# Ultrasonic_Localisation.net
KiCad netlist of a schematic drawn in Altium Designer
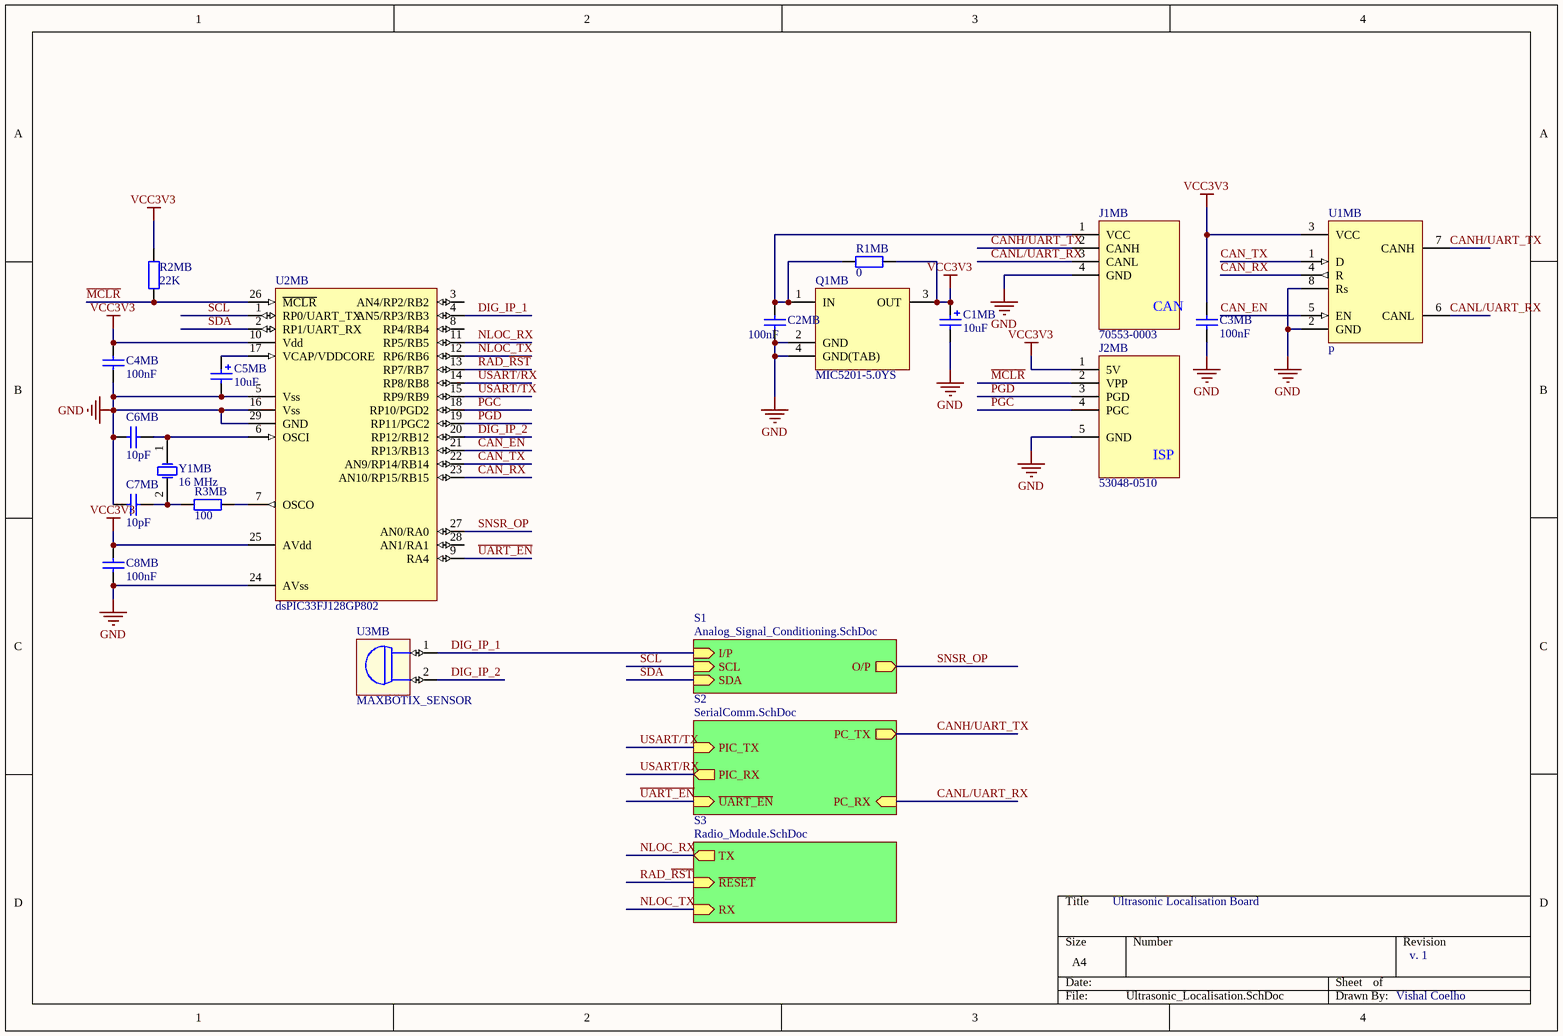
[diagram p0: Ultrasonic_Localisation.SchDoc]

(export (version "E")
  (design (tool "Eeschema 10.0.6"))
  (components
    (comp (ref "C1MB")
      (value "10uF")
      (footprint "TC3528-1411")
      (description "Polarized Capacitor (Surface Mount)")
      (fields (field (name "MANUFACTURER") "AVX") (field (name "Comment") "TPSB106K016R0800"))
      (libsource (lib "Comp") (part "Cap Pol"))
    )
    (comp (ref "C2MB")
      (value "100nF")
      (footprint "CC1608-0603")
      (description "Capacitor")
      (fields (field (name "MANUFACTURER") "Taiyo Yuden") (field (name "Comment") "UMK107BJ104KA-T"))
      (libsource (lib "Comp") (part "Cap"))
    )
    (comp (ref "C3MB")
      (value "100nF")
      (footprint "CC1608-0603")
      (description "Capacitor")
      (fields (field (name "MANUFACTURER") "Taiyo Yuden") (field (name "Comment") "UMK107BJ104KA-T"))
      (libsource (lib "Comp") (part "Cap"))
    )
    (comp (ref "C4MB")
      (value "100nF")
      (footprint "CC1608-0603")
      (description "Capacitor")
      (fields (field (name "MANUFACTURER") "Taiyo Yuden") (field (name "Comment") "UMK107BJ104KA-T"))
      (libsource (lib "Comp") (part "Cap"))
    )
    (comp (ref "C5MB")
      (value "10uF")
      (footprint "TC3528-1411")
      (description "Polarized Capacitor (Surface Mount)")
      (fields (field (name "MANUFACTURER") "AVX") (field (name "Comment") "TPSB106K016R0800"))
      (libsource (lib "Comp") (part "Cap Pol"))
    )
    (comp (ref "C6MB")
      (value "10pF")
      (footprint "CC1608-0603")
      (description "Capacitor")
      (fields (field (name "MANUFACTURER") "Panasonic") (field (name "Comment") "Cap"))
      (libsource (lib "Comp") (part "Cap"))
    )
    (comp (ref "C7MB")
      (value "10pF")
      (footprint "CC1608-0603")
      (description "Capacitor")
      (fields (field (name "MANUFACTURER") "Panasonic") (field (name "Comment") "Cap"))
      (libsource (lib "Comp") (part "Cap"))
    )
    (comp (ref "C8MB")
      (value "100nF")
      (footprint "CC1608-0603")
      (description "Capacitor")
      (fields (field (name "MANUFACTURER") "Taiyo Yuden") (field (name "Comment") "UMK107BJ104KA-T"))
      (libsource (lib "Comp") (part "Cap"))
    )
    (comp (ref "J1MB")
      (value "70553-0003")
      (footprint "CON_CAN_Device-4")
      (description "4 pin CAN Connector 2.54mm pitch")
      (fields (field (name "MANUFACTURER") "Molex"))
      (libsource (lib "Comp") (part "CON_CAN_DEVICE"))
    )
    (comp (ref "J2MB")
      (value "53048-0510")
      (footprint "CON_ISP")
      (description "6 pin header - 1.25mm pitch horizontal")
      (fields (field (name "MANUFACTURER") "Molex"))
      (libsource (lib "Comp") (part "CON_ISP_Header_5p_1.25mm_horizontal"))
    )
    (comp (ref "Q1MB")
      (value "MIC5201-5.0YS")
      (footprint "DSO-G3")
      (description "5V LDO 200mA")
      (fields (field (name "MANUFACTURER") "Micrel"))
      (libsource (lib "Comp") (part "MIC5201-5.0YS"))
    )
    (comp (ref "R1MB")
      (value "0")
      (footprint "CR1608-0603")
      (description "Resistor")
      (fields (field (name "Comment") "Res"))
      (libsource (lib "Comp") (part "Res"))
    )
    (comp (ref "R2MB")
      (value "22K")
      (footprint "CR1608-0603")
      (description "Resistor")
      (fields (field (name "Comment") "Res"))
      (libsource (lib "") (part "Res_1"))
    )
    (comp (ref "R3MB")
      (value "100")
      (footprint "CR1608-0603")
      (description "Resistor")
      (fields (field (name "Comment") "Res"))
      (libsource (lib "Comp") (part "Res"))
    )
    (comp (ref "U1MB")
      (value "p")
      (footprint "SO-G8/E2.9")
      (description "3.3V CAN Transceiver")
      (fields (field (name "MANUFACTURER") "Texas Instruments"))
      (libsource (lib "*") (part "SN65HVD234D"))
    )
    (comp (ref "U2MB")
      (value "dsPIC33FJ128GP802")
      (footprint "QFN6X6-28")
      (description "dsPIC33FJ128GP802 with 2 UART's")
      (fields (field (name "MANUFACTURER") "MicroChip"))
      (libsource (lib "Comp") (part "dsPIC33FJ128GP802"))
    )
    (comp (ref "U3MB")
      (value "MAXBOTIX_SENSOR")
      (footprint "Maxbotix Sensor")
      (description "Maxbotix Ultrasonic Sensor")
      (fields (field (name "MANUFACTURER") "Maxbotix"))
      (libsource (lib "*") (part "MAXBOTIX_SENSOR"))
    )
    (comp (ref "Y1MB")
      (value "16 MHz")
      (footprint "Footprints:CS10")
      (description "Crystal Oscillator")
      (fields (field (name "MANUFACTURER") "Citizen") (field (name "Comment") "CS10-16.000MABJ-UT"))
      (libsource (lib "Comp") (part "CS10"))
    )
  )
  (nets
    (net (code "1") (name "/CANH{slash}UART_TX") (class "Default")
      (node (ref "J1MB") (pin "2") (pinfunction "CANH_2") (pintype "passive"))
      (node (ref "U1MB") (pin "7") (pinfunction "CANH_7") (pintype "passive"))
    )
    (net (code "2") (name "/CANL{slash}UART_RX") (class "Default")
      (node (ref "J1MB") (pin "3") (pinfunction "CANL_3") (pintype "passive"))
      (node (ref "U1MB") (pin "6") (pinfunction "CANL_6") (pintype "passive"))
    )
    (net (code "3") (name "/CAN_EN") (class "Default")
      (node (ref "U1MB") (pin "5") (pinfunction "EN_5") (pintype "input"))
      (node (ref "U2MB") (pin "21") (pinfunction "RP13/RB13_21") (pintype "bidirectional"))
    )
    (net (code "4") (name "/CAN_RX") (class "Default")
      (node (ref "U1MB") (pin "4") (pinfunction "R_4") (pintype "output"))
      (node (ref "U2MB") (pin "23") (pinfunction "AN10/RP15/RB15_23") (pintype "bidirectional"))
    )
    (net (code "5") (name "/CAN_TX") (class "Default")
      (node (ref "U1MB") (pin "1") (pinfunction "D_1") (pintype "input"))
      (node (ref "U2MB") (pin "22") (pinfunction "AN9/RP14/RB14_22") (pintype "bidirectional"))
    )
    (net (code "6") (name "/DIG_IP_1") (class "Default")
      (node (ref "U2MB") (pin "4") (pinfunction "AN5/RP3/RB3_4") (pintype "bidirectional"))
      (node (ref "U3MB") (pin "1") (pinfunction "SNSR_1_1") (pintype "bidirectional"))
    )
    (net (code "7") (name "/DIG_IP_2") (class "Default")
      (node (ref "U2MB") (pin "20") (pinfunction "RP12/RB12_20") (pintype "bidirectional"))
      (node (ref "U3MB") (pin "2") (pinfunction "SNSR_2_2") (pintype "bidirectional"))
    )
    (net (code "8") (name "/NLOC_RX") (class "Default")
      (node (ref "U2MB") (pin "11") (pinfunction "RP5/RB5_11") (pintype "bidirectional"))
    )
    (net (code "9") (name "/NLOC_TX") (class "Default")
      (node (ref "U2MB") (pin "12") (pinfunction "RP6/RB6_12") (pintype "bidirectional"))
    )
    (net (code "10") (name "/PGC") (class "Default")
      (node (ref "J2MB") (pin "4") (pinfunction "PGC_4") (pintype "passive"))
      (node (ref "U2MB") (pin "18") (pinfunction "RP10/PGD2_18") (pintype "bidirectional"))
    )
    (net (code "11") (name "/PGD") (class "Default")
      (node (ref "J2MB") (pin "3") (pinfunction "PGD_3") (pintype "passive"))
      (node (ref "U2MB") (pin "19") (pinfunction "RP11/PGC2_19") (pintype "bidirectional"))
    )
    (net (code "12") (name "/RAD_~{RST}") (class "Default")
      (node (ref "U2MB") (pin "13") (pinfunction "RP7/RB7_13") (pintype "bidirectional"))
    )
    (net (code "13") (name "/SCL") (class "Default")
      (node (ref "U2MB") (pin "1") (pinfunction "RP0/UART_TX_1") (pintype "bidirectional"))
    )
    (net (code "14") (name "/SDA") (class "Default")
      (node (ref "U2MB") (pin "2") (pinfunction "RP1/UART_RX_2") (pintype "bidirectional"))
    )
    (net (code "15") (name "/SNSR_OP") (class "Default")
      (node (ref "U2MB") (pin "27") (pinfunction "AN0/RA0_27") (pintype "bidirectional"))
    )
    (net (code "16") (name "/USART{slash}RX") (class "Default")
      (node (ref "U2MB") (pin "14") (pinfunction "RP8/RB8_14") (pintype "bidirectional"))
    )
    (net (code "17") (name "/USART{slash}TX") (class "Default")
      (node (ref "U2MB") (pin "15") (pinfunction "RP9/RB9_15") (pintype "bidirectional"))
    )
    (net (code "18") (name "/~{MCLR}") (class "Default")
      (node (ref "J2MB") (pin "2") (pinfunction "VPP_2") (pintype "passive"))
      (node (ref "R2MB") (pin "1") (pinfunction "1_1") (pintype "passive"))
      (node (ref "U2MB") (pin "26") (pinfunction "~{MCLR}_26") (pintype "input"))
    )
    (net (code "19") (name "/~{UART_EN}") (class "Default")
      (node (ref "U2MB") (pin "9") (pinfunction "RA4_9") (pintype "bidirectional"))
    )
    (net (code "20") (name "GND") (class "Default")
      (node (ref "C1MB") (pin "2") (pinfunction "2_2") (pintype "passive"))
      (node (ref "C2MB") (pin "2") (pinfunction "2_2") (pintype "passive"))
      (node (ref "C3MB") (pin "2") (pinfunction "2_2") (pintype "passive"))
      (node (ref "C4MB") (pin "2") (pinfunction "2_2") (pintype "passive"))
      (node (ref "C5MB") (pin "2") (pinfunction "2_2") (pintype "passive"))
      (node (ref "C6MB") (pin "1") (pinfunction "1_1") (pintype "passive"))
      (node (ref "C7MB") (pin "1") (pinfunction "1_1") (pintype "passive"))
      (node (ref "C8MB") (pin "2") (pinfunction "2_2") (pintype "passive"))
      (node (ref "J1MB") (pin "4") (pinfunction "GND_4") (pintype "passive"))
      (node (ref "J2MB") (pin "5") (pinfunction "GND_5") (pintype "passive"))
      (node (ref "Q1MB") (pin "2") (pinfunction "GND_2") (pintype "power_in"))
      (node (ref "Q1MB") (pin "4") (pinfunction "GND(TAB)_4") (pintype "power_in"))
      (node (ref "U1MB") (pin "2") (pinfunction "GND_2") (pintype "power_in"))
      (node (ref "U1MB") (pin "8") (pinfunction "Rs_8") (pintype "passive"))
      (node (ref "U2MB") (pin "16") (pinfunction "Vss_16") (pintype "power_in"))
      (node (ref "U2MB") (pin "24") (pinfunction "AVss_24") (pintype "power_in"))
      (node (ref "U2MB") (pin "29") (pinfunction "GND_29") (pintype "power_in"))
      (node (ref "U2MB") (pin "5") (pinfunction "Vss_5") (pintype "power_in"))
    )
    (net (code "21") (name "Net-(J1MB-VCC)") (class "Default")
      (node (ref "C2MB") (pin "1") (pinfunction "1_1") (pintype "passive"))
      (node (ref "J1MB") (pin "1") (pinfunction "VCC_1") (pintype "passive"))
      (node (ref "Q1MB") (pin "1") (pinfunction "IN_1") (pintype "power_in"))
      (node (ref "R1MB") (pin "2") (pinfunction "2_2") (pintype "passive"))
    )
    (net (code "22") (name "Net-(U2MB-OSCI)") (class "Default")
      (node (ref "C6MB") (pin "2") (pinfunction "2_2") (pintype "passive"))
      (node (ref "U2MB") (pin "6") (pinfunction "OSCI_6") (pintype "input"))
      (node (ref "Y1MB") (pin "1") (pinfunction "OSC1_1") (pintype "passive"))
    )
    (net (code "23") (name "Net-(U2MB-OSCO)") (class "Default")
      (node (ref "R3MB") (pin "1") (pinfunction "1_1") (pintype "passive"))
      (node (ref "U2MB") (pin "7") (pinfunction "OSCO_7") (pintype "output"))
    )
    (net (code "24") (name "Net-(U2MB-VCAP{slash}VDDCORE)") (class "Default")
      (node (ref "C5MB") (pin "1") (pinfunction "1_1") (pintype "passive"))
      (node (ref "U2MB") (pin "17") (pinfunction "VCAP/VDDCORE_17") (pintype "input"))
    )
    (net (code "25") (name "Net-(Y1MB-OSC2)") (class "Default")
      (node (ref "C7MB") (pin "2") (pinfunction "2_2") (pintype "passive"))
      (node (ref "R3MB") (pin "2") (pinfunction "2_2") (pintype "passive"))
      (node (ref "Y1MB") (pin "2") (pinfunction "OSC2_2") (pintype "passive"))
    )
    (net (code "26") (name "VCC3V3") (class "Default")
      (node (ref "C1MB") (pin "1") (pinfunction "1_1") (pintype "passive"))
      (node (ref "C3MB") (pin "1") (pinfunction "1_1") (pintype "passive"))
      (node (ref "C4MB") (pin "1") (pinfunction "1_1") (pintype "passive"))
      (node (ref "C8MB") (pin "1") (pinfunction "1_1") (pintype "passive"))
      (node (ref "J2MB") (pin "1") (pinfunction "5V_1") (pintype "passive"))
      (node (ref "Q1MB") (pin "3") (pinfunction "OUT_3") (pintype "passive"))
      (node (ref "R1MB") (pin "1") (pinfunction "1_1") (pintype "passive"))
      (node (ref "R2MB") (pin "2") (pinfunction "2_2") (pintype "passive"))
      (node (ref "U1MB") (pin "3") (pinfunction "VCC_3") (pintype "power_in"))
      (node (ref "U2MB") (pin "10") (pinfunction "Vdd_10") (pintype "power_in"))
      (node (ref "U2MB") (pin "25") (pinfunction "AVdd_25") (pintype "power_in"))
    )
    (net (code "27") (name "unconnected-(U2MB-AN1{slash}RA1-Pad28)") (class "Default")
      (node (ref "U2MB") (pin "28") (pinfunction "AN1/RA1_28") (pintype "bidirectional"))
    )
    (net (code "28") (name "unconnected-(U2MB-AN4{slash}RP2{slash}RB2-Pad3)") (class "Default")
      (node (ref "U2MB") (pin "3") (pinfunction "AN4/RP2/RB2_3") (pintype "bidirectional"))
    )
    (net (code "29") (name "unconnected-(U2MB-RP4{slash}RB4-Pad8)") (class "Default")
      (node (ref "U2MB") (pin "8") (pinfunction "RP4/RB4_8") (pintype "bidirectional"))
    )
  )
)
